# HX711_ValveControl_Buzzer.net
KiCad netlist of a schematic drawn in EAGLE
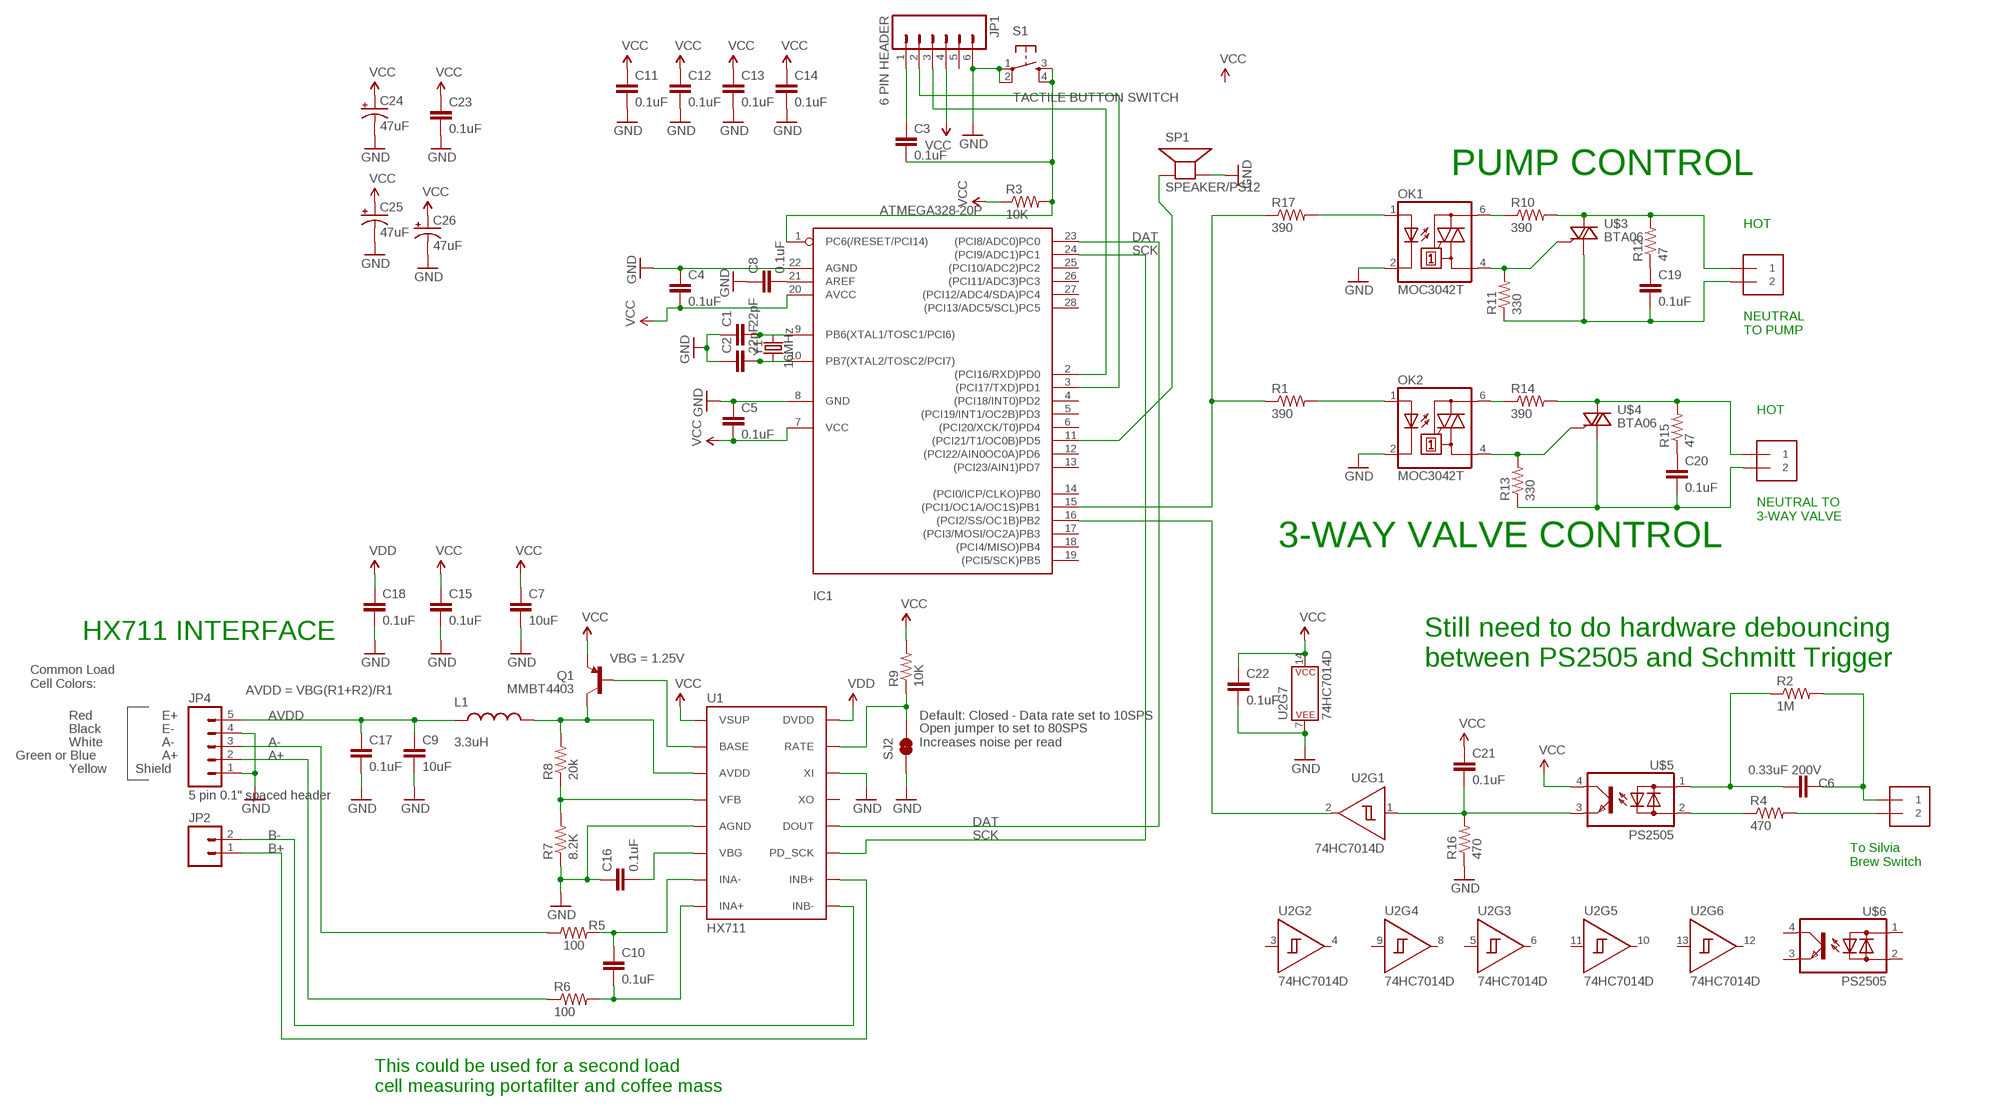
[diagram p0: schematic, sheet 1]

(export (version "E")
  (design (tool "Eeschema 10.0.6"))
  (components
    (comp (ref "C1")
      (value "22pF")
      (footprint "eagle-import:CAP-PTH-SMALL-KIT")
      (libsource (lib "eagle-import") (part "CAPKIT"))
    )
    (comp (ref "C2")
      (value "22pF")
      (footprint "eagle-import:CAP-PTH-SMALL-KIT")
      (libsource (lib "eagle-import") (part "CAPKIT"))
    )
    (comp (ref "C3")
      (value "0.1uF")
      (footprint "eagle-import:CAP-PTH-SMALLEZ")
      (libsource (lib "eagle-import") (part "CAPEZ"))
    )
    (comp (ref "C4")
      (value "0.1uF")
      (footprint "eagle-import:CAP-PTH-SMALLEZ")
      (libsource (lib "eagle-import") (part "CAPEZ"))
    )
    (comp (ref "C5")
      (value "0.1uF")
      (footprint "eagle-import:CAP-PTH-SMALLEZ")
      (libsource (lib "eagle-import") (part "CAPEZ"))
    )
    (comp (ref "C6")
      (value "0.33uF 200V")
      (footprint "eagle-import:C15B6")
      (libsource (lib "eagle-import") (part "C15/6"))
    )
    (comp (ref "C7")
      (value "10uF")
      (footprint "eagle-import:1210")
      (libsource (lib "eagle-import") (part "10UF50V20%(1210)"))
    )
    (comp (ref "C8")
      (value "0.1uF")
      (footprint "eagle-import:CAP-PTH-SMALLEZ")
      (libsource (lib "eagle-import") (part "CAPEZ"))
    )
    (comp (ref "C9")
      (value "10uF")
      (footprint "eagle-import:1210")
      (libsource (lib "eagle-import") (part "10UF50V20%(1210)"))
    )
    (comp (ref "C10")
      (value "0.1uF")
      (footprint "eagle-import:0603-CAP")
      (libsource (lib "eagle-import") (part "0.1UF-25V-5%(0603)"))
    )
    (comp (ref "C11")
      (value "0.1uF")
      (footprint "eagle-import:CAP-PTH-SMALLEZ")
      (libsource (lib "eagle-import") (part "CAPEZ"))
    )
    (comp (ref "C12")
      (value "0.1uF")
      (footprint "eagle-import:CAP-PTH-SMALLEZ")
      (libsource (lib "eagle-import") (part "CAPEZ"))
    )
    (comp (ref "C13")
      (value "0.1uF")
      (footprint "eagle-import:CAP-PTH-SMALLEZ")
      (libsource (lib "eagle-import") (part "CAPEZ"))
    )
    (comp (ref "C14")
      (value "0.1uF")
      (footprint "eagle-import:CAP-PTH-SMALLEZ")
      (libsource (lib "eagle-import") (part "CAPEZ"))
    )
    (comp (ref "C15")
      (value "0.1uF")
      (footprint "eagle-import:0603-CAP")
      (libsource (lib "eagle-import") (part "0.1UF-25V-5%(0603)"))
    )
    (comp (ref "C16")
      (value "0.1uF")
      (footprint "eagle-import:0603-CAP")
      (libsource (lib "eagle-import") (part "0.1UF-25V-5%(0603)"))
    )
    (comp (ref "C17")
      (value "0.1uF")
      (footprint "eagle-import:0603-CAP")
      (libsource (lib "eagle-import") (part "0.1UF-25V-5%(0603)"))
    )
    (comp (ref "C18")
      (value "0.1uF")
      (footprint "eagle-import:0603-CAP")
      (libsource (lib "eagle-import") (part "0.1UF-25V-5%(0603)"))
    )
    (comp (ref "C19")
      (value "0.1uF")
      (footprint "eagle-import:CAP-PTH-SMALLEZ")
      (libsource (lib "eagle-import") (part "CAPEZ"))
    )
    (comp (ref "C20")
      (value "0.1uF")
      (footprint "eagle-import:CAP-PTH-SMALLEZ")
      (libsource (lib "eagle-import") (part "CAPEZ"))
    )
    (comp (ref "C21")
      (value "0.1uF")
      (footprint "eagle-import:CAP-PTH-SMALLEZ")
      (libsource (lib "eagle-import") (part "CAPEZ"))
    )
    (comp (ref "C22")
      (value "0.1uF")
      (footprint "eagle-import:CAP-PTH-SMALLEZ")
      (libsource (lib "eagle-import") (part "CAPEZ"))
    )
    (comp (ref "C23")
      (value "0.1uF")
      (footprint "eagle-import:CAP-PTH-SMALLEZ")
      (libsource (lib "eagle-import") (part "CAPEZ"))
    )
    (comp (ref "C24")
      (value "47uF")
      (footprint "eagle-import:E5-8,5")
      (libsource (lib "eagle-import") (part "CPOL-USE5-8.5"))
    )
    (comp (ref "C25")
      (value "47uF")
      (footprint "eagle-import:E5-8,5")
      (libsource (lib "eagle-import") (part "CPOL-USE5-8.5"))
    )
    (comp (ref "C26")
      (value "47uF")
      (footprint "eagle-import:E5-8,5")
      (libsource (lib "eagle-import") (part "CPOL-USE5-8.5"))
    )
    (comp (ref "IC1")
      (value "ATMEGA328-20P")
      (footprint "eagle-import:DIL28-3")
      (libsource (lib "eagle-import") (part "ATMEGA328P-20"))
    )
    (comp (ref "J2")
      (value "1X2-3.5MM")
      (footprint "eagle-import:1X2-3.5MM")
      (libsource (lib "eagle-import") (part "1X2-3.5MM"))
    )
    (comp (ref "J3")
      (value "1X2-3.5MM")
      (footprint "eagle-import:1X2-3.5MM")
      (libsource (lib "eagle-import") (part "1X2-3.5MM"))
    )
    (comp (ref "J4")
      (value "1X2-3.5MM")
      (footprint "eagle-import:1X2-3.5MM")
      (libsource (lib "eagle-import") (part "1X2-3.5MM"))
    )
    (comp (ref "JP1")
      (value "6 PIN HEADER")
      (footprint "eagle-import:1X06_LOCK_LONGPADS")
      (libsource (lib "eagle-import") (part "M06LOCK_LONGPADS"))
    )
    (comp (ref "JP2")
      (value "M02PTH")
      (footprint "eagle-import:1X02")
      (libsource (lib "eagle-import") (part "M02PTH"))
    )
    (comp (ref "JP4")
      (value "5 pin 0.1\" spaced header")
      (footprint "eagle-import:1X05")
      (libsource (lib "eagle-import") (part "M05PTH"))
    )
    (comp (ref "L1")
      (value "3.3uH")
      (footprint "eagle-import:0805")
      (libsource (lib "eagle-import") (part "INDUCTOR0805-IND"))
    )
    (comp (ref "OK1")
      (value "MOC3042T")
      (footprint "eagle-import:DIL06B")
      (libsource (lib "eagle-import") (part "MOC30T42"))
    )
    (comp (ref "OK2")
      (value "MOC3042T")
      (footprint "eagle-import:DIL06B")
      (libsource (lib "eagle-import") (part "MOC30T42"))
    )
    (comp (ref "Q1")
      (value "MMBT4403")
      (footprint "eagle-import:SOT23-3")
      (libsource (lib "eagle-import") (part "TRANSISTOR_PNPMMBT4403"))
    )
    (comp (ref "R1")
      (value "390")
      (footprint "eagle-import:AXIAL-0.5")
      (libsource (lib "eagle-import") (part "RESISTORPTH-1/2W"))
    )
    (comp (ref "R2")
      (value "1M")
      (footprint "eagle-import:1_6W-RES")
      (libsource (lib "eagle-import") (part "RESISTORPTH-1/6W"))
    )
    (comp (ref "R3")
      (value "10K")
      (footprint "eagle-import:AXIAL-0.5")
      (libsource (lib "eagle-import") (part "RESISTORPTH-1/2W"))
    )
    (comp (ref "R4")
      (value "470")
      (footprint "eagle-import:AXIAL-0.3-KIT")
      (libsource (lib "eagle-import") (part "RESISTORKIT"))
    )
    (comp (ref "R5")
      (value "100")
      (footprint "eagle-import:0603-RES")
      (libsource (lib "eagle-import") (part "100OHM-1/10W-1%(0603)"))
    )
    (comp (ref "R6")
      (value "100")
      (footprint "eagle-import:0603-RES")
      (libsource (lib "eagle-import") (part "100OHM-1/10W-1%(0603)"))
    )
    (comp (ref "R7")
      (value "8.2K")
      (footprint "eagle-import:0603-RES")
      (libsource (lib "eagle-import") (part "8.2KOHM-1/10W-5%(0603)"))
    )
    (comp (ref "R8")
      (value "20k")
      (footprint "eagle-import:0603-RES")
      (libsource (lib "eagle-import") (part "20KOHM1/10W1%(0603)"))
    )
    (comp (ref "R9")
      (value "10K")
      (footprint "eagle-import:0603-RES")
      (libsource (lib "eagle-import") (part "10KOHM-1/10W-1%(0603)0603"))
    )
    (comp (ref "R10")
      (value "390")
      (footprint "eagle-import:AXIAL-0.5")
      (libsource (lib "eagle-import") (part "RESISTORPTH-1/2W"))
    )
    (comp (ref "R11")
      (value "330")
      (footprint "eagle-import:AXIAL-0.5")
      (libsource (lib "eagle-import") (part "RESISTORPTH-1/2W"))
    )
    (comp (ref "R12")
      (value "47")
      (footprint "eagle-import:AXIAL-0.5")
      (libsource (lib "eagle-import") (part "RESISTORPTH-1/2W"))
    )
    (comp (ref "R13")
      (value "330")
      (footprint "eagle-import:AXIAL-0.5")
      (libsource (lib "eagle-import") (part "RESISTORPTH-1/2W"))
    )
    (comp (ref "R14")
      (value "390")
      (footprint "eagle-import:AXIAL-0.5")
      (libsource (lib "eagle-import") (part "RESISTORPTH-1/2W"))
    )
    (comp (ref "R15")
      (value "47")
      (footprint "eagle-import:AXIAL-0.5")
      (libsource (lib "eagle-import") (part "RESISTORPTH-1/2W"))
    )
    (comp (ref "R16")
      (value "470")
      (footprint "eagle-import:AXIAL-0.5")
      (libsource (lib "eagle-import") (part "RESISTORPTH-1/2W"))
    )
    (comp (ref "R17")
      (value "390")
      (footprint "eagle-import:AXIAL-0.5")
      (libsource (lib "eagle-import") (part "RESISTORPTH-1/2W"))
    )
    (comp (ref "S1")
      (value "TACTILE BUTTON SWITCH")
      (footprint "eagle-import:TACTILE-PTH")
      (libsource (lib "eagle-import") (part "TAC_SWITCHPTH"))
    )
    (comp (ref "SJ2")
      (value "JUMPER-PAD-2-NC_BY_TRACE")
      (footprint "eagle-import:PAD-JUMPER-2-NC_BY_TRACE_YES_SILK")
      (libsource (lib "eagle-import") (part "JUMPER-PAD-2-NC_BY_TRACE"))
    )
    (comp (ref "SP1")
      (value "SPEAKER/PS12")
      (footprint "eagle-import:PS12")
      (libsource (lib "eagle-import") (part "SPEAKER/PS12"))
    )
    (comp (ref "U$3")
      (value "BTA06")
      (footprint "eagle-import:TO220V")
      (libsource (lib "eagle-import") (part "BTA06"))
    )
    (comp (ref "U$4")
      (value "BTA06")
      (footprint "eagle-import:TO220V")
      (libsource (lib "eagle-import") (part "BTA06"))
    )
    (comp (ref "U$5")
      (value "PS2505")
      (footprint "eagle-import:DIL04")
      (libsource (lib "eagle-import") (part "PS2505"))
    )
    (comp (ref "U$6")
      (value "PS2505")
      (footprint "eagle-import:DIL04")
      (libsource (lib "eagle-import") (part "PS2505"))
    )
    (comp (ref "U1")
      (value "HX711")
      (footprint "eagle-import:SO16")
      (libsource (lib "eagle-import") (part "HX711HX711"))
    )
    (comp (ref "U2")
      (value "74HC7014D")
      (footprint "eagle-import:SO14")
      (libsource (lib "eagle-import") (part "747014DHC"))
    )
    (comp (ref "Y1")
      (value "16MHz")
      (footprint "eagle-import:HC49US")
      (libsource (lib "eagle-import") (part "CRYSTAL-16MHZPTH-HC49US"))
    )
  )
  (nets
    (net (code "1") (name "/A+") (class "Default")
      (node (ref "JP4") (pin "2") (pinfunction "2_2") (pintype "passive"))
      (node (ref "R6") (pin "1") (pinfunction "1_1") (pintype "passive"))
    )
    (net (code "2") (name "/A-") (class "Default")
      (node (ref "JP4") (pin "3") (pinfunction "3_3") (pintype "passive"))
      (node (ref "R5") (pin "1") (pinfunction "1_1") (pintype "passive"))
    )
    (net (code "3") (name "/AVDD") (class "Default")
      (node (ref "C17") (pin "1") (pinfunction "1_1") (pintype "passive"))
      (node (ref "C9") (pin "1") (pinfunction "1_1") (pintype "passive"))
      (node (ref "JP4") (pin "5") (pinfunction "5_5") (pintype "passive"))
      (node (ref "L1") (pin "1") (pinfunction "1_1") (pintype "passive"))
    )
    (net (code "4") (name "/B+") (class "Default")
      (node (ref "JP2") (pin "1") (pinfunction "1_1") (pintype "passive"))
      (node (ref "U1") (pin "10") (pinfunction "INB+_10") (pintype "bidirectional"))
    )
    (net (code "5") (name "/B-") (class "Default")
      (node (ref "JP2") (pin "2") (pinfunction "2_2") (pintype "passive"))
      (node (ref "U1") (pin "9") (pinfunction "INB-_9") (pintype "bidirectional"))
    )
    (net (code "6") (name "/DAT") (class "Default")
      (node (ref "IC1") (pin "23") (pinfunction "(PCI8/ADC0)PC0_23") (pintype "bidirectional"))
      (node (ref "U1") (pin "12") (pinfunction "DOUT_12") (pintype "bidirectional"))
    )
    (net (code "7") (name "/SCK") (class "Default")
      (node (ref "IC1") (pin "24") (pinfunction "(PCI9/ADC1)PC1_24") (pintype "bidirectional"))
      (node (ref "U1") (pin "11") (pinfunction "PD_SCK_11") (pintype "bidirectional"))
    )
    (net (code "8") (name "GND") (class "Default")
      (node (ref "C1") (pin "1") (pinfunction "1_1") (pintype "passive"))
      (node (ref "C11") (pin "2") (pinfunction "2_2") (pintype "passive"))
      (node (ref "C12") (pin "2") (pinfunction "2_2") (pintype "passive"))
      (node (ref "C13") (pin "2") (pinfunction "2_2") (pintype "passive"))
      (node (ref "C14") (pin "2") (pinfunction "2_2") (pintype "passive"))
      (node (ref "C15") (pin "2") (pinfunction "2_2") (pintype "passive"))
      (node (ref "C16") (pin "1") (pinfunction "1_1") (pintype "passive"))
      (node (ref "C17") (pin "2") (pinfunction "2_2") (pintype "passive"))
      (node (ref "C18") (pin "2") (pinfunction "2_2") (pintype "passive"))
      (node (ref "C2") (pin "1") (pinfunction "1_1") (pintype "passive"))
      (node (ref "C22") (pin "2") (pinfunction "2_2") (pintype "passive"))
      (node (ref "C23") (pin "2") (pinfunction "2_2") (pintype "passive"))
      (node (ref "C24") (pin "-") (pinfunction "-_-") (pintype "passive"))
      (node (ref "C25") (pin "-") (pinfunction "-_-") (pintype "passive"))
      (node (ref "C26") (pin "-") (pinfunction "-_-") (pintype "passive"))
      (node (ref "C4") (pin "1") (pinfunction "1_1") (pintype "passive"))
      (node (ref "C5") (pin "1") (pinfunction "1_1") (pintype "passive"))
      (node (ref "C7") (pin "2") (pinfunction "2_2") (pintype "passive"))
      (node (ref "C8") (pin "1") (pinfunction "1_1") (pintype "passive"))
      (node (ref "C9") (pin "2") (pinfunction "2_2") (pintype "passive"))
      (node (ref "IC1") (pin "22") (pinfunction "AGND_22") (pintype "bidirectional"))
      (node (ref "IC1") (pin "8") (pinfunction "GND_8") (pintype "bidirectional"))
      (node (ref "JP1") (pin "6") (pinfunction "6_6") (pintype "passive"))
      (node (ref "JP4") (pin "1") (pinfunction "1_1") (pintype "passive"))
      (node (ref "JP4") (pin "4") (pinfunction "4_4") (pintype "passive"))
      (node (ref "OK1") (pin "2") (pinfunction "C_2") (pintype "passive"))
      (node (ref "OK2") (pin "2") (pinfunction "C_2") (pintype "passive"))
      (node (ref "R16") (pin "P$1") (pinfunction "1_P$1") (pintype "passive"))
      (node (ref "R7") (pin "1") (pinfunction "1_1") (pintype "passive"))
      (node (ref "S1") (pin "1") (pinfunction "1_1") (pintype "passive"))
      (node (ref "S1") (pin "2") (pinfunction "2_2") (pintype "passive"))
      (node (ref "SJ2") (pin "1") (pinfunction "1_1") (pintype "passive"))
      (node (ref "SP1") (pin "P$2") (pinfunction "-_P$2") (pintype "passive"))
      (node (ref "U1") (pin "14") (pinfunction "XI_14") (pintype "bidirectional"))
      (node (ref "U1") (pin "5") (pinfunction "AGND_5") (pintype "bidirectional"))
      (node (ref "U2") (pin "7") (pinfunction "P$V-_7") (pintype "bidirectional"))
    )
    (net (code "9") (name "Net-(C3-Pad1)") (class "Default")
      (node (ref "C3") (pin "1") (pinfunction "1_1") (pintype "passive"))
      (node (ref "JP1") (pin "1") (pinfunction "1_1") (pintype "passive"))
    )
    (net (code "10") (name "Net-(C6-Pad2)") (class "Default")
      (node (ref "C6") (pin "2") (pinfunction "2_2") (pintype "passive"))
      (node (ref "J2") (pin "1") (pinfunction "1_1") (pintype "passive"))
      (node (ref "R2") (pin "2") (pinfunction "2_2") (pintype "passive"))
    )
    (net (code "11") (name "Net-(IC1-(PCI1{slash}OC1A{slash}OC1S)PB1)") (class "Default")
      (node (ref "IC1") (pin "15") (pinfunction "(PCI1/OC1A/OC1S)PB1_15") (pintype "bidirectional"))
      (node (ref "R1") (pin "P$1") (pinfunction "1_P$1") (pintype "passive"))
      (node (ref "R17") (pin "P$1") (pinfunction "1_P$1") (pintype "passive"))
    )
    (net (code "12") (name "Net-(IC1-(PCI2{slash}SS{slash}OC1B)PB2)") (class "Default")
      (node (ref "IC1") (pin "16") (pinfunction "(PCI2/SS/OC1B)PB2_16") (pintype "bidirectional"))
      (node (ref "U2") (pin "2") (pinfunction "Y_2") (pintype "bidirectional"))
    )
    (net (code "13") (name "Net-(IC1-(PCI16{slash}RXD)PD0)") (class "Default")
      (node (ref "IC1") (pin "2") (pinfunction "(PCI16/RXD)PD0_2") (pintype "bidirectional"))
      (node (ref "JP1") (pin "3") (pinfunction "3_3") (pintype "passive"))
    )
    (net (code "14") (name "Net-(IC1-(PCI17{slash}TXD)PD1)") (class "Default")
      (node (ref "IC1") (pin "3") (pinfunction "(PCI17/TXD)PD1_3") (pintype "bidirectional"))
      (node (ref "JP1") (pin "2") (pinfunction "2_2") (pintype "passive"))
    )
    (net (code "15") (name "Net-(IC1-(PCI21{slash}T1{slash}OC0B)PD5)") (class "Default")
      (node (ref "IC1") (pin "11") (pinfunction "(PCI21/T1/OC0B)PD5_11") (pintype "bidirectional"))
      (node (ref "SP1") (pin "P$1") (pinfunction "+_P$1") (pintype "passive"))
    )
    (net (code "16") (name "Net-(IC1-AREF)") (class "Default")
      (node (ref "C8") (pin "2") (pinfunction "2_2") (pintype "passive"))
      (node (ref "IC1") (pin "21") (pinfunction "AREF_21") (pintype "bidirectional"))
    )
    (net (code "17") (name "Net-(IC1-PB6(XTAL1{slash}TOSC1{slash}PCI6))") (class "Default")
      (node (ref "C1") (pin "2") (pinfunction "2_2") (pintype "passive"))
      (node (ref "IC1") (pin "9") (pinfunction "PB6(XTAL1/TOSC1/PCI6)_9") (pintype "bidirectional"))
      (node (ref "Y1") (pin "2") (pinfunction "2_2") (pintype "passive"))
    )
    (net (code "18") (name "Net-(IC1-PB7(XTAL2{slash}TOSC2{slash}PCI7))") (class "Default")
      (node (ref "C2") (pin "2") (pinfunction "2_2") (pintype "passive"))
      (node (ref "IC1") (pin "10") (pinfunction "PB7(XTAL2/TOSC2/PCI7)_10") (pintype "bidirectional"))
      (node (ref "Y1") (pin "1") (pinfunction "1_1") (pintype "passive"))
    )
    (net (code "19") (name "Net-(IC1-PC6({slash}RESET{slash}PCI14))") (class "Default")
      (node (ref "C3") (pin "2") (pinfunction "2_2") (pintype "passive"))
      (node (ref "IC1") (pin "1") (pinfunction "PC6(/RESET/PCI14)_1") (pintype "bidirectional"))
      (node (ref "R3") (pin "P$2") (pinfunction "2_P$2") (pintype "passive"))
      (node (ref "S1") (pin "3") (pinfunction "3_3") (pintype "passive"))
      (node (ref "S1") (pin "4") (pinfunction "4_4") (pintype "passive"))
    )
    (net (code "20") (name "Net-(OK1-A)") (class "Default")
      (node (ref "OK1") (pin "1") (pinfunction "A_1") (pintype "passive"))
      (node (ref "R17") (pin "P$2") (pinfunction "2_P$2") (pintype "passive"))
    )
    (net (code "21") (name "Net-(OK1-A1)") (class "Default")
      (node (ref "OK1") (pin "4") (pinfunction "A1_4") (pintype "passive"))
      (node (ref "R11") (pin "P$2") (pinfunction "2_P$2") (pintype "passive"))
      (node (ref "U$3") (pin "3") (pinfunction "G_3") (pintype "passive"))
    )
    (net (code "22") (name "Net-(OK1-A2)") (class "Default")
      (node (ref "OK1") (pin "6") (pinfunction "A2_6") (pintype "passive"))
      (node (ref "R10") (pin "P$1") (pinfunction "1_P$1") (pintype "passive"))
    )
    (net (code "23") (name "Net-(OK2-A)") (class "Default")
      (node (ref "OK2") (pin "1") (pinfunction "A_1") (pintype "passive"))
      (node (ref "R1") (pin "P$2") (pinfunction "2_P$2") (pintype "passive"))
    )
    (net (code "24") (name "Net-(OK2-A1)") (class "Default")
      (node (ref "OK2") (pin "4") (pinfunction "A1_4") (pintype "passive"))
      (node (ref "R13") (pin "P$2") (pinfunction "2_P$2") (pintype "passive"))
      (node (ref "U$4") (pin "3") (pinfunction "G_3") (pintype "passive"))
    )
    (net (code "25") (name "Net-(OK2-A2)") (class "Default")
      (node (ref "OK2") (pin "6") (pinfunction "A2_6") (pintype "passive"))
      (node (ref "R14") (pin "P$1") (pinfunction "1_P$1") (pintype "passive"))
    )
    (net (code "26") (name "Net-(Q1-B)") (class "Default")
      (node (ref "Q1") (pin "1") (pinfunction "B_1") (pintype "passive"))
      (node (ref "U1") (pin "2") (pinfunction "BASE_2") (pintype "bidirectional"))
    )
    (net (code "27") (name "Net-(Q1-C)") (class "Default")
      (node (ref "L1") (pin "2") (pinfunction "2_2") (pintype "passive"))
      (node (ref "Q1") (pin "3") (pinfunction "C_3") (pintype "passive"))
      (node (ref "R8") (pin "2") (pinfunction "2_2") (pintype "passive"))
      (node (ref "U1") (pin "3") (pinfunction "AVDD_3") (pintype "bidirectional"))
    )
    (net (code "28") (name "Net-(R4-1)") (class "Default")
      (node (ref "R4") (pin "P$1") (pinfunction "1_P$1") (pintype "passive"))
      (node (ref "U$5") (pin "2") (pinfunction "AC2_2") (pintype "passive"))
    )
    (net (code "29") (name "Net-(R4-2)") (class "Default")
      (node (ref "J2") (pin "2") (pinfunction "2_2") (pintype "passive"))
      (node (ref "R4") (pin "P$2") (pinfunction "2_P$2") (pintype "passive"))
    )
    (net (code "30") (name "Net-(R10-2)") (class "Default")
      (node (ref "J3") (pin "1") (pinfunction "1_1") (pintype "passive"))
      (node (ref "R10") (pin "P$2") (pinfunction "2_P$2") (pintype "passive"))
      (node (ref "R12") (pin "P$2") (pinfunction "2_P$2") (pintype "passive"))
      (node (ref "U$3") (pin "2") (pinfunction "A2_2") (pintype "passive"))
    )
    (net (code "31") (name "Net-(R11-1)") (class "Default")
      (node (ref "C19") (pin "2") (pinfunction "2_2") (pintype "passive"))
      (node (ref "J3") (pin "2") (pinfunction "2_2") (pintype "passive"))
      (node (ref "R11") (pin "P$1") (pinfunction "1_P$1") (pintype "passive"))
      (node (ref "U$3") (pin "1") (pinfunction "A1_1") (pintype "passive"))
    )
    (net (code "32") (name "Net-(R12-1)") (class "Default")
      (node (ref "C19") (pin "1") (pinfunction "1_1") (pintype "passive"))
      (node (ref "R12") (pin "P$1") (pinfunction "1_P$1") (pintype "passive"))
    )
    (net (code "33") (name "Net-(R13-1)") (class "Default")
      (node (ref "C20") (pin "2") (pinfunction "2_2") (pintype "passive"))
      (node (ref "J4") (pin "2") (pinfunction "2_2") (pintype "passive"))
      (node (ref "R13") (pin "P$1") (pinfunction "1_P$1") (pintype "passive"))
      (node (ref "U$4") (pin "1") (pinfunction "A1_1") (pintype "passive"))
    )
    (net (code "34") (name "Net-(R14-2)") (class "Default")
      (node (ref "J4") (pin "1") (pinfunction "1_1") (pintype "passive"))
      (node (ref "R14") (pin "P$2") (pinfunction "2_P$2") (pintype "passive"))
      (node (ref "R15") (pin "P$2") (pinfunction "2_P$2") (pintype "passive"))
      (node (ref "U$4") (pin "2") (pinfunction "A2_2") (pintype "passive"))
    )
    (net (code "35") (name "Net-(R15-1)") (class "Default")
      (node (ref "C20") (pin "1") (pinfunction "1_1") (pintype "passive"))
      (node (ref "R15") (pin "P$1") (pinfunction "1_P$1") (pintype "passive"))
    )
    (net (code "36") (name "Net-(R16-2)") (class "Default")
      (node (ref "C21") (pin "2") (pinfunction "2_2") (pintype "passive"))
      (node (ref "R16") (pin "P$2") (pinfunction "2_P$2") (pintype "passive"))
      (node (ref "U$5") (pin "3") (pinfunction "E_3") (pintype "passive"))
      (node (ref "U2") (pin "1") (pinfunction "A_1") (pintype "bidirectional"))
    )
    (net (code "37") (name "Net-(U$5-AC1)") (class "Default")
      (node (ref "C6") (pin "1") (pinfunction "1_1") (pintype "passive"))
      (node (ref "R2") (pin "1") (pinfunction "1_1") (pintype "passive"))
      (node (ref "U$5") (pin "1") (pinfunction "AC1_1") (pintype "passive"))
    )
    (net (code "38") (name "Net-(U1-INA+)") (class "Default")
      (node (ref "C10") (pin "2") (pinfunction "2_2") (pintype "passive"))
      (node (ref "R6") (pin "2") (pinfunction "2_2") (pintype "passive"))
      (node (ref "U1") (pin "8") (pinfunction "INA+_8") (pintype "bidirectional"))
    )
    (net (code "39") (name "Net-(U1-INA-)") (class "Default")
      (node (ref "C10") (pin "1") (pinfunction "1_1") (pintype "passive"))
      (node (ref "R5") (pin "2") (pinfunction "2_2") (pintype "passive"))
      (node (ref "U1") (pin "7") (pinfunction "INA-_7") (pintype "bidirectional"))
    )
    (net (code "40") (name "Net-(U1-RATE)") (class "Default")
      (node (ref "R9") (pin "1") (pinfunction "1_1") (pintype "passive"))
      (node (ref "SJ2") (pin "2") (pinfunction "2_2") (pintype "passive"))
      (node (ref "U1") (pin "15") (pinfunction "RATE_15") (pintype "bidirectional"))
    )
    (net (code "41") (name "Net-(U1-VBG)") (class "Default")
      (node (ref "C16") (pin "2") (pinfunction "2_2") (pintype "passive"))
      (node (ref "U1") (pin "6") (pinfunction "VBG_6") (pintype "bidirectional"))
    )
    (net (code "42") (name "Net-(U1-VFB)") (class "Default")
      (node (ref "R7") (pin "2") (pinfunction "2_2") (pintype "passive"))
      (node (ref "R8") (pin "1") (pinfunction "1_1") (pintype "passive"))
      (node (ref "U1") (pin "4") (pinfunction "VFB_4") (pintype "bidirectional"))
    )
    (net (code "43") (name "VCC") (class "Default")
      (node (ref "C11") (pin "1") (pinfunction "1_1") (pintype "passive"))
      (node (ref "C12") (pin "1") (pinfunction "1_1") (pintype "passive"))
      (node (ref "C13") (pin "1") (pinfunction "1_1") (pintype "passive"))
      (node (ref "C14") (pin "1") (pinfunction "1_1") (pintype "passive"))
      (node (ref "C15") (pin "1") (pinfunction "1_1") (pintype "passive"))
      (node (ref "C21") (pin "1") (pinfunction "1_1") (pintype "passive"))
      (node (ref "C22") (pin "1") (pinfunction "1_1") (pintype "passive"))
      (node (ref "C23") (pin "1") (pinfunction "1_1") (pintype "passive"))
      (node (ref "C24") (pin "+") (pinfunction "+_+") (pintype "passive"))
      (node (ref "C25") (pin "+") (pinfunction "+_+") (pintype "passive"))
      (node (ref "C26") (pin "+") (pinfunction "+_+") (pintype "passive"))
      (node (ref "C4") (pin "2") (pinfunction "2_2") (pintype "passive"))
      (node (ref "C5") (pin "2") (pinfunction "2_2") (pintype "passive"))
      (node (ref "C7") (pin "1") (pinfunction "1_1") (pintype "passive"))
      (node (ref "IC1") (pin "20") (pinfunction "AVCC_20") (pintype "bidirectional"))
      (node (ref "IC1") (pin "7") (pinfunction "VCC_7") (pintype "bidirectional"))
      (node (ref "JP1") (pin "4") (pinfunction "4_4") (pintype "passive"))
      (node (ref "Q1") (pin "2") (pinfunction "E_2") (pintype "passive"))
      (node (ref "R3") (pin "P$1") (pinfunction "1_P$1") (pintype "passive"))
      (node (ref "R9") (pin "2") (pinfunction "2_2") (pintype "passive"))
      (node (ref "U$5") (pin "4") (pinfunction "C_4") (pintype "passive"))
      (node (ref "U1") (pin "1") (pinfunction "VSUP_1") (pintype "bidirectional"))
      (node (ref "U2") (pin "14") (pinfunction "P$V+_14") (pintype "bidirectional"))
    )
    (net (code "44") (name "VDD") (class "Default")
      (node (ref "C18") (pin "1") (pinfunction "1_1") (pintype "passive"))
      (node (ref "U1") (pin "16") (pinfunction "DVDD_16") (pintype "bidirectional"))
    )
    (net (code "45") (name "unconnected-(IC1-(PCI0{slash}ICP{slash}CLKO)PB0-Pad14)") (class "Default")
      (node (ref "IC1") (pin "14") (pinfunction "(PCI0/ICP/CLKO)PB0_14") (pintype "bidirectional"))
    )
    (net (code "46") (name "unconnected-(IC1-(PCI3{slash}MOSI{slash}OC2A)PB3-Pad17)") (class "Default")
      (node (ref "IC1") (pin "17") (pinfunction "(PCI3/MOSI/OC2A)PB3_17") (pintype "bidirectional"))
    )
    (net (code "47") (name "unconnected-(IC1-(PCI4{slash}MISO)PB4-Pad18)") (class "Default")
      (node (ref "IC1") (pin "18") (pinfunction "(PCI4/MISO)PB4_18") (pintype "bidirectional"))
    )
    (net (code "48") (name "unconnected-(IC1-(PCI5{slash}SCK)PB5-Pad19)") (class "Default")
      (node (ref "IC1") (pin "19") (pinfunction "(PCI5/SCK)PB5_19") (pintype "bidirectional"))
    )
    (net (code "49") (name "unconnected-(IC1-(PCI10{slash}ADC2)PC2-Pad25)") (class "Default")
      (node (ref "IC1") (pin "25") (pinfunction "(PCI10/ADC2)PC2_25") (pintype "bidirectional"))
    )
    (net (code "50") (name "unconnected-(IC1-(PCI11{slash}ADC3)PC3-Pad26)") (class "Default")
      (node (ref "IC1") (pin "26") (pinfunction "(PCI11/ADC3)PC3_26") (pintype "bidirectional"))
    )
    (net (code "51") (name "unconnected-(IC1-(PCI12{slash}ADC4{slash}SDA)PC4-Pad27)") (class "Default")
      (node (ref "IC1") (pin "27") (pinfunction "(PCI12/ADC4/SDA)PC4_27") (pintype "bidirectional"))
    )
    (net (code "52") (name "unconnected-(IC1-(PCI13{slash}ADC5{slash}SCL)PC5-Pad28)") (class "Default")
      (node (ref "IC1") (pin "28") (pinfunction "(PCI13/ADC5/SCL)PC5_28") (pintype "bidirectional"))
    )
    (net (code "53") (name "unconnected-(IC1-(PCI18{slash}INT0)PD2-Pad4)") (class "Default")
      (node (ref "IC1") (pin "4") (pinfunction "(PCI18/INT0)PD2_4") (pintype "bidirectional"))
    )
    (net (code "54") (name "unconnected-(IC1-(PCI19{slash}INT1{slash}OC2B)PD3-Pad5)") (class "Default")
      (node (ref "IC1") (pin "5") (pinfunction "(PCI19/INT1/OC2B)PD3_5") (pintype "bidirectional"))
    )
    (net (code "55") (name "unconnected-(IC1-(PCI20{slash}XCK{slash}T0)PD4-Pad6)") (class "Default")
      (node (ref "IC1") (pin "6") (pinfunction "(PCI20/XCK/T0)PD4_6") (pintype "bidirectional"))
    )
    (net (code "56") (name "unconnected-(IC1-(PCI22{slash}AIN0OC0A)PD6-Pad12)") (class "Default")
      (node (ref "IC1") (pin "12") (pinfunction "(PCI22/AIN0OC0A)PD6_12") (pintype "bidirectional"))
    )
    (net (code "57") (name "unconnected-(IC1-(PCI23{slash}AIN1)PD7-Pad13)") (class "Default")
      (node (ref "IC1") (pin "13") (pinfunction "(PCI23/AIN1)PD7_13") (pintype "bidirectional"))
    )
    (net (code "58") (name "unconnected-(JP1-Pad5)") (class "Default")
      (node (ref "JP1") (pin "5") (pinfunction "5_5") (pintype "passive"))
    )
    (net (code "59") (name "unconnected-(U$6-AC1-Pad1)") (class "Default")
      (node (ref "U$6") (pin "1") (pinfunction "AC1_1") (pintype "passive"))
    )
    (net (code "60") (name "unconnected-(U$6-AC2-Pad2)") (class "Default")
      (node (ref "U$6") (pin "2") (pinfunction "AC2_2") (pintype "passive"))
    )
    (net (code "61") (name "unconnected-(U$6-C-Pad4)") (class "Default")
      (node (ref "U$6") (pin "4") (pinfunction "C_4") (pintype "passive"))
    )
    (net (code "62") (name "unconnected-(U$6-E-Pad3)") (class "Default")
      (node (ref "U$6") (pin "3") (pinfunction "E_3") (pintype "passive"))
    )
    (net (code "63") (name "unconnected-(U1-XO-Pad13)") (class "Default")
      (node (ref "U1") (pin "13") (pinfunction "XO_13") (pintype "bidirectional"))
    )
    (net (code "64") (name "unconnected-(U2B-A-Pad3)") (class "Default")
      (node (ref "U2") (pin "3") (pinfunction "A_3") (pintype "bidirectional"))
    )
    (net (code "65") (name "unconnected-(U2B-Y-Pad4)") (class "Default")
      (node (ref "U2") (pin "4") (pinfunction "Y_4") (pintype "bidirectional"))
    )
    (net (code "66") (name "unconnected-(U2C-A-Pad5)") (class "Default")
      (node (ref "U2") (pin "5") (pinfunction "A_5") (pintype "bidirectional"))
    )
    (net (code "67") (name "unconnected-(U2C-Y-Pad6)") (class "Default")
      (node (ref "U2") (pin "6") (pinfunction "Y_6") (pintype "bidirectional"))
    )
    (net (code "68") (name "unconnected-(U2D-A-Pad9)") (class "Default")
      (node (ref "U2") (pin "9") (pinfunction "A_9") (pintype "bidirectional"))
    )
    (net (code "69") (name "unconnected-(U2D-Y-Pad8)") (class "Default")
      (node (ref "U2") (pin "8") (pinfunction "Y_8") (pintype "bidirectional"))
    )
    (net (code "70") (name "unconnected-(U2E-A-Pad11)") (class "Default")
      (node (ref "U2") (pin "11") (pinfunction "A_11") (pintype "bidirectional"))
    )
    (net (code "71") (name "unconnected-(U2E-Y-Pad10)") (class "Default")
      (node (ref "U2") (pin "10") (pinfunction "Y_10") (pintype "bidirectional"))
    )
    (net (code "72") (name "unconnected-(U2F-A-Pad13)") (class "Default")
      (node (ref "U2") (pin "13") (pinfunction "A_13") (pintype "bidirectional"))
    )
    (net (code "73") (name "unconnected-(U2F-Y-Pad12)") (class "Default")
      (node (ref "U2") (pin "12") (pinfunction "Y_12") (pintype "bidirectional"))
    )
  )
)
